# BSU_BQ796XX.net
KiCad netlist of a schematic drawn in Altium Designer
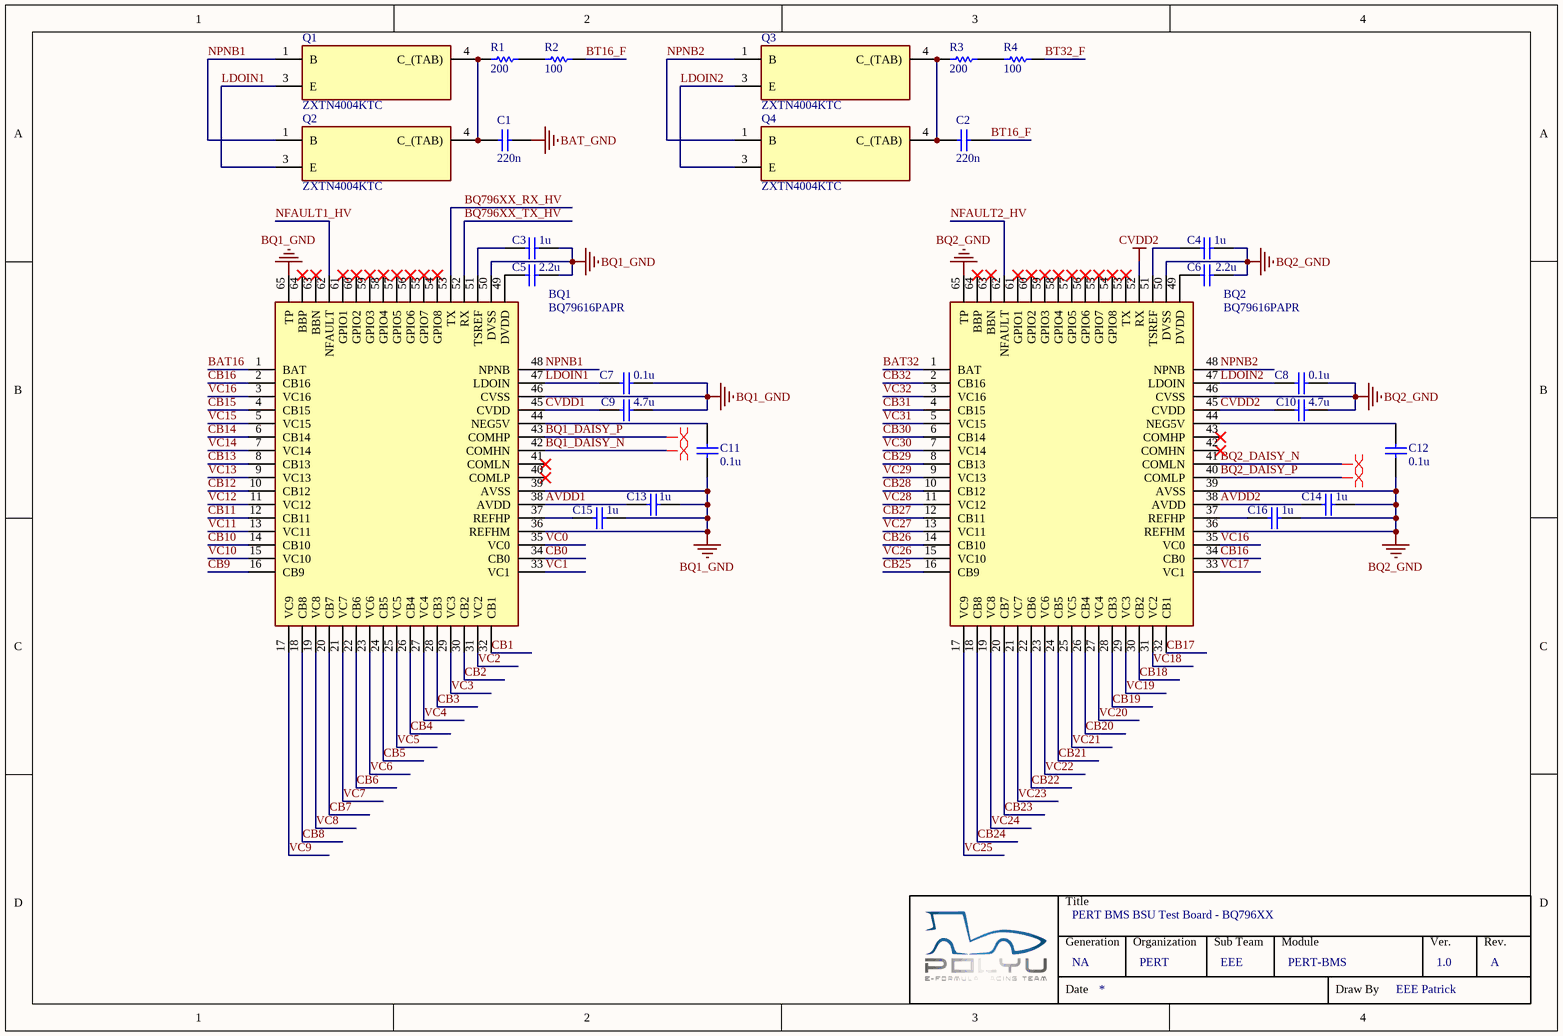
[diagram p0: BSU_BQ796XX.SchDoc]

(export (version "E")
  (design (tool "Eeschema 10.0.6"))
  (components
    (comp (ref "BQ1")
      (value "BQ79616PAPR")
      (footprint "HTQFP65_BQ79616")
      (fields (field (name "MOUSER PART NUMBER") "595-BQ79616PAPR"))
      (libsource (lib "BMS_ShareComponentLibrary") (part "BQ79616PAPR"))
    )
    (comp (ref "BQ2")
      (value "BQ79616PAPR")
      (footprint "HTQFP65_BQ79616")
      (fields (field (name "MOUSER PART NUMBER") "595-BQ79616PAPR"))
      (libsource (lib "BMS_ShareComponentLibrary") (part "BQ79616PAPR"))
    )
    (comp (ref "C1")
      (value "220n")
      (footprint "1210_SMD_C")
      (description "1210 SMD Capacitor")
      (libsource (lib "BMS_ShareComponentLibrary") (part "1210_SMD_Capacitor"))
    )
    (comp (ref "C2")
      (value "220n")
      (footprint "1210_SMD_C")
      (description "1210 SMD Capacitor")
      (libsource (lib "BMS_ShareComponentLibrary") (part "1210_SMD_Capacitor"))
    )
    (comp (ref "C3")
      (value "1u")
      (footprint "0603_SMD_C")
      (description "0603 SMD Capacitor")
      (libsource (lib "BMS_ShareComponentLibrary") (part "0603_SMD_Capacitor"))
    )
    (comp (ref "C4")
      (value "1u")
      (footprint "0603_SMD_C")
      (description "0603 SMD Capacitor")
      (libsource (lib "BMS_ShareComponentLibrary") (part "0603_SMD_Capacitor"))
    )
    (comp (ref "C5")
      (value "2.2u")
      (footprint "0603_SMD_C")
      (description "0603 SMD Capacitor")
      (libsource (lib "BMS_ShareComponentLibrary") (part "0603_SMD_Capacitor"))
    )
    (comp (ref "C6")
      (value "2.2u")
      (footprint "0603_SMD_C")
      (description "0603 SMD Capacitor")
      (libsource (lib "BMS_ShareComponentLibrary") (part "0603_SMD_Capacitor"))
    )
    (comp (ref "C7")
      (value "0.1u")
      (footprint "0603_SMD_C")
      (description "0603 SMD Capacitor")
      (libsource (lib "BMS_ShareComponentLibrary") (part "0603_SMD_Capacitor"))
    )
    (comp (ref "C8")
      (value "0.1u")
      (footprint "0603_SMD_C")
      (description "0603 SMD Capacitor")
      (libsource (lib "BMS_ShareComponentLibrary") (part "0603_SMD_Capacitor"))
    )
    (comp (ref "C9")
      (value "4.7u")
      (footprint "0603_SMD_C")
      (description "0603 SMD Capacitor")
      (libsource (lib "BMS_ShareComponentLibrary") (part "0603_SMD_Capacitor"))
    )
    (comp (ref "C10")
      (value "4.7u")
      (footprint "0603_SMD_C")
      (description "0603 SMD Capacitor")
      (libsource (lib "BMS_ShareComponentLibrary") (part "0603_SMD_Capacitor"))
    )
    (comp (ref "C11")
      (value "0.1u")
      (footprint "0603_SMD_C")
      (description "0603 SMD Capacitor")
      (libsource (lib "BMS_ShareComponentLibrary") (part "0603_SMD_Capacitor"))
    )
    (comp (ref "C12")
      (value "0.1u")
      (footprint "0603_SMD_C")
      (description "0603 SMD Capacitor")
      (libsource (lib "BMS_ShareComponentLibrary") (part "0603_SMD_Capacitor"))
    )
    (comp (ref "C13")
      (value "1u")
      (footprint "0603_SMD_C")
      (description "0603 SMD Capacitor")
      (libsource (lib "BMS_ShareComponentLibrary") (part "0603_SMD_Capacitor"))
    )
    (comp (ref "C14")
      (value "1u")
      (footprint "0603_SMD_C")
      (description "0603 SMD Capacitor")
      (libsource (lib "BMS_ShareComponentLibrary") (part "0603_SMD_Capacitor"))
    )
    (comp (ref "C15")
      (value "1u")
      (footprint "0603_SMD_C")
      (description "0603 SMD Capacitor")
      (libsource (lib "BMS_ShareComponentLibrary") (part "0603_SMD_Capacitor"))
    )
    (comp (ref "C16")
      (value "1u")
      (footprint "0603_SMD_C")
      (description "0603 SMD Capacitor")
      (libsource (lib "BMS_ShareComponentLibrary") (part "0603_SMD_Capacitor"))
    )
    (comp (ref "Q1")
      (value "ZXTN4004KTC")
      (footprint "TO252-3_ZXTN4004K")
      (description "Transistor")
      (fields (field (name "MOUSER PART NUMBER") "621-ZXTN4004KTC"))
      (libsource (lib "BMS_ShareComponentLibrary") (part "ZXTN4004KTC"))
    )
    (comp (ref "Q2")
      (value "ZXTN4004KTC")
      (footprint "TO252-3_ZXTN4004K")
      (description "Transistor")
      (fields (field (name "MOUSER PART NUMBER") "621-ZXTN4004KTC"))
      (libsource (lib "BMS_ShareComponentLibrary") (part "ZXTN4004KTC"))
    )
    (comp (ref "Q3")
      (value "ZXTN4004KTC")
      (footprint "TO252-3_ZXTN4004K")
      (description "Transistor")
      (fields (field (name "MOUSER PART NUMBER") "621-ZXTN4004KTC"))
      (libsource (lib "BMS_ShareComponentLibrary") (part "ZXTN4004KTC"))
    )
    (comp (ref "Q4")
      (value "ZXTN4004KTC")
      (footprint "TO252-3_ZXTN4004K")
      (description "Transistor")
      (fields (field (name "MOUSER PART NUMBER") "621-ZXTN4004KTC"))
      (libsource (lib "BMS_ShareComponentLibrary") (part "ZXTN4004KTC"))
    )
    (comp (ref "R1")
      (value "200")
      (footprint "2010_SMD_R")
      (description "2010 SMD Resistor")
      (libsource (lib "BMS_ShareComponentLibrary") (part "2010_SMD_Resistor"))
    )
    (comp (ref "R2")
      (value "100")
      (footprint "2010_SMD_R")
      (description "2010 SMD Resistor")
      (libsource (lib "BMS_ShareComponentLibrary") (part "2010_SMD_Resistor"))
    )
    (comp (ref "R3")
      (value "200")
      (footprint "2010_SMD_R")
      (description "2010 SMD Resistor")
      (libsource (lib "BMS_ShareComponentLibrary") (part "2010_SMD_Resistor"))
    )
    (comp (ref "R4")
      (value "100")
      (footprint "2010_SMD_R")
      (description "2010 SMD Resistor")
      (libsource (lib "BMS_ShareComponentLibrary") (part "2010_SMD_Resistor"))
    )
  )
  (nets
    (net (code "1") (name "/AVDD1") (class "Default")
      (node (ref "BQ1") (pin "38") (pinfunction "AVDD_38") (pintype "passive"))
      (node (ref "C13") (pin "2") (pinfunction "2_2") (pintype "passive"))
    )
    (net (code "2") (name "/AVDD2") (class "Default")
      (node (ref "BQ2") (pin "38") (pinfunction "AVDD_38") (pintype "passive"))
      (node (ref "C14") (pin "2") (pinfunction "2_2") (pintype "passive"))
    )
    (net (code "3") (name "/BAT16") (class "Default")
      (node (ref "BQ1") (pin "1") (pinfunction "BAT_1") (pintype "passive"))
    )
    (net (code "4") (name "/BAT32") (class "Default")
      (node (ref "BQ2") (pin "1") (pinfunction "BAT_1") (pintype "passive"))
    )
    (net (code "5") (name "/BQ1_DAISY_N") (class "Default")
      (node (ref "BQ1") (pin "42") (pinfunction "COMHN_42") (pintype "passive"))
    )
    (net (code "6") (name "/BQ1_DAISY_P") (class "Default")
      (node (ref "BQ1") (pin "43") (pinfunction "COMHP_43") (pintype "passive"))
    )
    (net (code "7") (name "/BQ2_DAISY_N") (class "Default")
      (node (ref "BQ2") (pin "41") (pinfunction "COMLN_41") (pintype "passive"))
    )
    (net (code "8") (name "/BQ2_DAISY_P") (class "Default")
      (node (ref "BQ2") (pin "40") (pinfunction "COMLP_40") (pintype "passive"))
    )
    (net (code "9") (name "/BQ796XX_RX_HV") (class "Default")
      (node (ref "BQ1") (pin "53") (pinfunction "TX_53") (pintype "passive"))
    )
    (net (code "10") (name "/BQ796XX_TX_HV") (class "Default")
      (node (ref "BQ1") (pin "52") (pinfunction "RX_52") (pintype "passive"))
    )
    (net (code "11") (name "/BT16_F") (class "Default")
      (node (ref "C2") (pin "2") (pinfunction "2_2") (pintype "passive"))
      (node (ref "R2") (pin "2") (pinfunction "2_2") (pintype "passive"))
    )
    (net (code "12") (name "/BT32_F") (class "Default")
      (node (ref "R4") (pin "2") (pinfunction "2_2") (pintype "passive"))
    )
    (net (code "13") (name "/CB0") (class "Default")
      (node (ref "BQ1") (pin "34") (pinfunction "CB0_34") (pintype "passive"))
    )
    (net (code "14") (name "/CB1") (class "Default")
      (node (ref "BQ1") (pin "32") (pinfunction "CB1_32") (pintype "passive"))
    )
    (net (code "15") (name "/CB2") (class "Default")
      (node (ref "BQ1") (pin "30") (pinfunction "CB2_30") (pintype "passive"))
    )
    (net (code "16") (name "/CB3") (class "Default")
      (node (ref "BQ1") (pin "28") (pinfunction "CB3_28") (pintype "passive"))
    )
    (net (code "17") (name "/CB4") (class "Default")
      (node (ref "BQ1") (pin "26") (pinfunction "CB4_26") (pintype "passive"))
    )
    (net (code "18") (name "/CB5") (class "Default")
      (node (ref "BQ1") (pin "24") (pinfunction "CB5_24") (pintype "passive"))
    )
    (net (code "19") (name "/CB6") (class "Default")
      (node (ref "BQ1") (pin "22") (pinfunction "CB6_22") (pintype "passive"))
    )
    (net (code "20") (name "/CB7") (class "Default")
      (node (ref "BQ1") (pin "20") (pinfunction "CB7_20") (pintype "passive"))
    )
    (net (code "21") (name "/CB8") (class "Default")
      (node (ref "BQ1") (pin "18") (pinfunction "CB8_18") (pintype "passive"))
    )
    (net (code "22") (name "/CB9") (class "Default")
      (node (ref "BQ1") (pin "16") (pinfunction "CB9_16") (pintype "passive"))
    )
    (net (code "23") (name "/CB10") (class "Default")
      (node (ref "BQ1") (pin "14") (pinfunction "CB10_14") (pintype "passive"))
    )
    (net (code "24") (name "/CB11") (class "Default")
      (node (ref "BQ1") (pin "12") (pinfunction "CB11_12") (pintype "passive"))
    )
    (net (code "25") (name "/CB12") (class "Default")
      (node (ref "BQ1") (pin "10") (pinfunction "CB12_10") (pintype "passive"))
    )
    (net (code "26") (name "/CB13") (class "Default")
      (node (ref "BQ1") (pin "8") (pinfunction "CB13_8") (pintype "passive"))
    )
    (net (code "27") (name "/CB14") (class "Default")
      (node (ref "BQ1") (pin "6") (pinfunction "CB14_6") (pintype "passive"))
    )
    (net (code "28") (name "/CB15") (class "Default")
      (node (ref "BQ1") (pin "4") (pinfunction "CB15_4") (pintype "passive"))
    )
    (net (code "29") (name "/CB16") (class "Default")
      (node (ref "BQ1") (pin "2") (pinfunction "CB16_2") (pintype "passive"))
      (node (ref "BQ2") (pin "34") (pinfunction "CB0_34") (pintype "passive"))
    )
    (net (code "30") (name "/CB17") (class "Default")
      (node (ref "BQ2") (pin "32") (pinfunction "CB1_32") (pintype "passive"))
    )
    (net (code "31") (name "/CB18") (class "Default")
      (node (ref "BQ2") (pin "30") (pinfunction "CB2_30") (pintype "passive"))
    )
    (net (code "32") (name "/CB19") (class "Default")
      (node (ref "BQ2") (pin "28") (pinfunction "CB3_28") (pintype "passive"))
    )
    (net (code "33") (name "/CB20") (class "Default")
      (node (ref "BQ2") (pin "26") (pinfunction "CB4_26") (pintype "passive"))
    )
    (net (code "34") (name "/CB21") (class "Default")
      (node (ref "BQ2") (pin "24") (pinfunction "CB5_24") (pintype "passive"))
    )
    (net (code "35") (name "/CB22") (class "Default")
      (node (ref "BQ2") (pin "22") (pinfunction "CB6_22") (pintype "passive"))
    )
    (net (code "36") (name "/CB23") (class "Default")
      (node (ref "BQ2") (pin "20") (pinfunction "CB7_20") (pintype "passive"))
    )
    (net (code "37") (name "/CB24") (class "Default")
      (node (ref "BQ2") (pin "18") (pinfunction "CB8_18") (pintype "passive"))
    )
    (net (code "38") (name "/CB25") (class "Default")
      (node (ref "BQ2") (pin "16") (pinfunction "CB9_16") (pintype "passive"))
    )
    (net (code "39") (name "/CB26") (class "Default")
      (node (ref "BQ2") (pin "14") (pinfunction "CB10_14") (pintype "passive"))
    )
    (net (code "40") (name "/CB27") (class "Default")
      (node (ref "BQ2") (pin "12") (pinfunction "CB11_12") (pintype "passive"))
    )
    (net (code "41") (name "/CB28") (class "Default")
      (node (ref "BQ2") (pin "10") (pinfunction "CB12_10") (pintype "passive"))
    )
    (net (code "42") (name "/CB29") (class "Default")
      (node (ref "BQ2") (pin "8") (pinfunction "CB13_8") (pintype "passive"))
    )
    (net (code "43") (name "/CB30") (class "Default")
      (node (ref "BQ2") (pin "6") (pinfunction "CB14_6") (pintype "passive"))
    )
    (net (code "44") (name "/CB31") (class "Default")
      (node (ref "BQ2") (pin "4") (pinfunction "CB15_4") (pintype "passive"))
    )
    (net (code "45") (name "/CB32") (class "Default")
      (node (ref "BQ2") (pin "2") (pinfunction "CB16_2") (pintype "passive"))
    )
    (net (code "46") (name "/CVDD1") (class "Default")
      (node (ref "BQ1") (pin "45") (pinfunction "CVDD_45") (pintype "passive"))
      (node (ref "C9") (pin "1") (pinfunction "1_1") (pintype "passive"))
    )
    (net (code "47") (name "/LDOIN1") (class "Default")
      (node (ref "BQ1") (pin "47") (pinfunction "LDOIN_47") (pintype "passive"))
      (node (ref "C7") (pin "2") (pinfunction "2_2") (pintype "passive"))
      (node (ref "Q1") (pin "3") (pinfunction "E_3") (pintype "passive"))
      (node (ref "Q2") (pin "3") (pinfunction "E_3") (pintype "passive"))
    )
    (net (code "48") (name "/LDOIN2") (class "Default")
      (node (ref "BQ2") (pin "47") (pinfunction "LDOIN_47") (pintype "passive"))
      (node (ref "C8") (pin "2") (pinfunction "2_2") (pintype "passive"))
      (node (ref "Q3") (pin "3") (pinfunction "E_3") (pintype "passive"))
      (node (ref "Q4") (pin "3") (pinfunction "E_3") (pintype "passive"))
    )
    (net (code "49") (name "/NFAULT1_HV") (class "Default")
      (node (ref "BQ1") (pin "62") (pinfunction "NFAULT_62") (pintype "passive"))
    )
    (net (code "50") (name "/NFAULT2_HV") (class "Default")
      (node (ref "BQ2") (pin "62") (pinfunction "NFAULT_62") (pintype "passive"))
    )
    (net (code "51") (name "/NPNB1") (class "Default")
      (node (ref "BQ1") (pin "48") (pinfunction "NPNB_48") (pintype "passive"))
      (node (ref "Q1") (pin "1") (pinfunction "B_1") (pintype "passive"))
      (node (ref "Q2") (pin "1") (pinfunction "B_1") (pintype "passive"))
    )
    (net (code "52") (name "/NPNB2") (class "Default")
      (node (ref "BQ2") (pin "48") (pinfunction "NPNB_48") (pintype "passive"))
      (node (ref "Q3") (pin "1") (pinfunction "B_1") (pintype "passive"))
      (node (ref "Q4") (pin "1") (pinfunction "B_1") (pintype "passive"))
    )
    (net (code "53") (name "/VC0") (class "Default")
      (node (ref "BQ1") (pin "35") (pinfunction "VC0_35") (pintype "passive"))
    )
    (net (code "54") (name "/VC1") (class "Default")
      (node (ref "BQ1") (pin "33") (pinfunction "VC1_33") (pintype "passive"))
    )
    (net (code "55") (name "/VC2") (class "Default")
      (node (ref "BQ1") (pin "31") (pinfunction "VC2_31") (pintype "passive"))
    )
    (net (code "56") (name "/VC3") (class "Default")
      (node (ref "BQ1") (pin "29") (pinfunction "VC3_29") (pintype "passive"))
    )
    (net (code "57") (name "/VC4") (class "Default")
      (node (ref "BQ1") (pin "27") (pinfunction "VC4_27") (pintype "passive"))
    )
    (net (code "58") (name "/VC5") (class "Default")
      (node (ref "BQ1") (pin "25") (pinfunction "VC5_25") (pintype "passive"))
    )
    (net (code "59") (name "/VC6") (class "Default")
      (node (ref "BQ1") (pin "23") (pinfunction "VC6_23") (pintype "passive"))
    )
    (net (code "60") (name "/VC7") (class "Default")
      (node (ref "BQ1") (pin "21") (pinfunction "VC7_21") (pintype "passive"))
    )
    (net (code "61") (name "/VC8") (class "Default")
      (node (ref "BQ1") (pin "19") (pinfunction "VC8_19") (pintype "passive"))
    )
    (net (code "62") (name "/VC9") (class "Default")
      (node (ref "BQ1") (pin "17") (pinfunction "VC9_17") (pintype "passive"))
    )
    (net (code "63") (name "/VC10") (class "Default")
      (node (ref "BQ1") (pin "15") (pinfunction "VC10_15") (pintype "passive"))
    )
    (net (code "64") (name "/VC11") (class "Default")
      (node (ref "BQ1") (pin "13") (pinfunction "VC11_13") (pintype "passive"))
    )
    (net (code "65") (name "/VC12") (class "Default")
      (node (ref "BQ1") (pin "11") (pinfunction "VC12_11") (pintype "passive"))
    )
    (net (code "66") (name "/VC13") (class "Default")
      (node (ref "BQ1") (pin "9") (pinfunction "VC13_9") (pintype "passive"))
    )
    (net (code "67") (name "/VC14") (class "Default")
      (node (ref "BQ1") (pin "7") (pinfunction "VC14_7") (pintype "passive"))
    )
    (net (code "68") (name "/VC15") (class "Default")
      (node (ref "BQ1") (pin "5") (pinfunction "VC15_5") (pintype "passive"))
    )
    (net (code "69") (name "/VC16") (class "Default")
      (node (ref "BQ1") (pin "3") (pinfunction "VC16_3") (pintype "passive"))
      (node (ref "BQ2") (pin "35") (pinfunction "VC0_35") (pintype "passive"))
    )
    (net (code "70") (name "/VC17") (class "Default")
      (node (ref "BQ2") (pin "33") (pinfunction "VC1_33") (pintype "passive"))
    )
    (net (code "71") (name "/VC18") (class "Default")
      (node (ref "BQ2") (pin "31") (pinfunction "VC2_31") (pintype "passive"))
    )
    (net (code "72") (name "/VC19") (class "Default")
      (node (ref "BQ2") (pin "29") (pinfunction "VC3_29") (pintype "passive"))
    )
    (net (code "73") (name "/VC20") (class "Default")
      (node (ref "BQ2") (pin "27") (pinfunction "VC4_27") (pintype "passive"))
    )
    (net (code "74") (name "/VC21") (class "Default")
      (node (ref "BQ2") (pin "25") (pinfunction "VC5_25") (pintype "passive"))
    )
    (net (code "75") (name "/VC22") (class "Default")
      (node (ref "BQ2") (pin "23") (pinfunction "VC6_23") (pintype "passive"))
    )
    (net (code "76") (name "/VC23") (class "Default")
      (node (ref "BQ2") (pin "21") (pinfunction "VC7_21") (pintype "passive"))
    )
    (net (code "77") (name "/VC24") (class "Default")
      (node (ref "BQ2") (pin "19") (pinfunction "VC8_19") (pintype "passive"))
    )
    (net (code "78") (name "/VC25") (class "Default")
      (node (ref "BQ2") (pin "17") (pinfunction "VC9_17") (pintype "passive"))
    )
    (net (code "79") (name "/VC26") (class "Default")
      (node (ref "BQ2") (pin "15") (pinfunction "VC10_15") (pintype "passive"))
    )
    (net (code "80") (name "/VC27") (class "Default")
      (node (ref "BQ2") (pin "13") (pinfunction "VC11_13") (pintype "passive"))
    )
    (net (code "81") (name "/VC28") (class "Default")
      (node (ref "BQ2") (pin "11") (pinfunction "VC12_11") (pintype "passive"))
    )
    (net (code "82") (name "/VC29") (class "Default")
      (node (ref "BQ2") (pin "9") (pinfunction "VC13_9") (pintype "passive"))
    )
    (net (code "83") (name "/VC30") (class "Default")
      (node (ref "BQ2") (pin "7") (pinfunction "VC14_7") (pintype "passive"))
    )
    (net (code "84") (name "/VC31") (class "Default")
      (node (ref "BQ2") (pin "5") (pinfunction "VC15_5") (pintype "passive"))
    )
    (net (code "85") (name "/VC32") (class "Default")
      (node (ref "BQ2") (pin "3") (pinfunction "VC16_3") (pintype "passive"))
    )
    (net (code "86") (name "BAT_GND") (class "Default")
      (node (ref "C1") (pin "2") (pinfunction "2_2") (pintype "passive"))
    )
    (net (code "87") (name "BQ1_GND") (class "Default")
      (node (ref "BQ1") (pin "36") (pinfunction "REFHM_36") (pintype "passive"))
      (node (ref "BQ1") (pin "39") (pinfunction "AVSS_39") (pintype "passive"))
      (node (ref "BQ1") (pin "46") (pinfunction "CVSS_46") (pintype "passive"))
      (node (ref "BQ1") (pin "50") (pinfunction "DVSS_50") (pintype "passive"))
      (node (ref "BQ1") (pin "65") (pinfunction "TP_65") (pintype "passive"))
      (node (ref "C11") (pin "1") (pinfunction "1_1") (pintype "passive"))
      (node (ref "C13") (pin "1") (pinfunction "1_1") (pintype "passive"))
      (node (ref "C15") (pin "1") (pinfunction "1_1") (pintype "passive"))
      (node (ref "C3") (pin "2") (pinfunction "2_2") (pintype "passive"))
      (node (ref "C5") (pin "2") (pinfunction "2_2") (pintype "passive"))
      (node (ref "C7") (pin "1") (pinfunction "1_1") (pintype "passive"))
      (node (ref "C9") (pin "2") (pinfunction "2_2") (pintype "passive"))
    )
    (net (code "88") (name "BQ2_GND") (class "Default")
      (node (ref "BQ2") (pin "36") (pinfunction "REFHM_36") (pintype "passive"))
      (node (ref "BQ2") (pin "39") (pinfunction "AVSS_39") (pintype "passive"))
      (node (ref "BQ2") (pin "46") (pinfunction "CVSS_46") (pintype "passive"))
      (node (ref "BQ2") (pin "50") (pinfunction "DVSS_50") (pintype "passive"))
      (node (ref "BQ2") (pin "65") (pinfunction "TP_65") (pintype "passive"))
      (node (ref "C10") (pin "2") (pinfunction "2_2") (pintype "passive"))
      (node (ref "C12") (pin "1") (pinfunction "1_1") (pintype "passive"))
      (node (ref "C14") (pin "1") (pinfunction "1_1") (pintype "passive"))
      (node (ref "C16") (pin "1") (pinfunction "1_1") (pintype "passive"))
      (node (ref "C4") (pin "2") (pinfunction "2_2") (pintype "passive"))
      (node (ref "C6") (pin "2") (pinfunction "2_2") (pintype "passive"))
      (node (ref "C8") (pin "1") (pinfunction "1_1") (pintype "passive"))
    )
    (net (code "89") (name "CVDD2") (class "Default")
      (node (ref "BQ2") (pin "45") (pinfunction "CVDD_45") (pintype "passive"))
      (node (ref "BQ2") (pin "52") (pinfunction "RX_52") (pintype "passive"))
      (node (ref "C10") (pin "1") (pinfunction "1_1") (pintype "passive"))
    )
    (net (code "90") (name "Net-(BQ1-DVDD)") (class "Default")
      (node (ref "BQ1") (pin "49") (pinfunction "DVDD_49") (pintype "passive"))
      (node (ref "C5") (pin "1") (pinfunction "1_1") (pintype "passive"))
    )
    (net (code "91") (name "Net-(BQ1-NEG5V)") (class "Default")
      (node (ref "BQ1") (pin "44") (pinfunction "NEG5V_44") (pintype "passive"))
      (node (ref "C11") (pin "2") (pinfunction "2_2") (pintype "passive"))
    )
    (net (code "92") (name "Net-(BQ1-REFHP)") (class "Default")
      (node (ref "BQ1") (pin "37") (pinfunction "REFHP_37") (pintype "passive"))
      (node (ref "C15") (pin "2") (pinfunction "2_2") (pintype "passive"))
    )
    (net (code "93") (name "Net-(BQ1-TSREF)") (class "Default")
      (node (ref "BQ1") (pin "51") (pinfunction "TSREF_51") (pintype "passive"))
      (node (ref "C3") (pin "1") (pinfunction "1_1") (pintype "passive"))
    )
    (net (code "94") (name "Net-(BQ2-DVDD)") (class "Default")
      (node (ref "BQ2") (pin "49") (pinfunction "DVDD_49") (pintype "passive"))
      (node (ref "C6") (pin "1") (pinfunction "1_1") (pintype "passive"))
    )
    (net (code "95") (name "Net-(BQ2-NEG5V)") (class "Default")
      (node (ref "BQ2") (pin "44") (pinfunction "NEG5V_44") (pintype "passive"))
      (node (ref "C12") (pin "2") (pinfunction "2_2") (pintype "passive"))
    )
    (net (code "96") (name "Net-(BQ2-REFHP)") (class "Default")
      (node (ref "BQ2") (pin "37") (pinfunction "REFHP_37") (pintype "passive"))
      (node (ref "C16") (pin "2") (pinfunction "2_2") (pintype "passive"))
    )
    (net (code "97") (name "Net-(BQ2-TSREF)") (class "Default")
      (node (ref "BQ2") (pin "51") (pinfunction "TSREF_51") (pintype "passive"))
      (node (ref "C4") (pin "1") (pinfunction "1_1") (pintype "passive"))
    )
    (net (code "98") (name "Net-(Q1-C_(TAB))") (class "Default")
      (node (ref "C1") (pin "1") (pinfunction "1_1") (pintype "passive"))
      (node (ref "Q1") (pin "4") (pinfunction "C_(TAB)_4") (pintype "passive"))
      (node (ref "Q2") (pin "4") (pinfunction "C_(TAB)_4") (pintype "passive"))
      (node (ref "R1") (pin "1") (pinfunction "1_1") (pintype "passive"))
    )
    (net (code "99") (name "Net-(Q3-C_(TAB))") (class "Default")
      (node (ref "C2") (pin "1") (pinfunction "1_1") (pintype "passive"))
      (node (ref "Q3") (pin "4") (pinfunction "C_(TAB)_4") (pintype "passive"))
      (node (ref "Q4") (pin "4") (pinfunction "C_(TAB)_4") (pintype "passive"))
      (node (ref "R3") (pin "1") (pinfunction "1_1") (pintype "passive"))
    )
    (net (code "100") (name "Net-(R1-Pad2)") (class "Default")
      (node (ref "R1") (pin "2") (pinfunction "2_2") (pintype "passive"))
      (node (ref "R2") (pin "1") (pinfunction "1_1") (pintype "passive"))
    )
    (net (code "101") (name "Net-(R3-Pad2)") (class "Default")
      (node (ref "R3") (pin "2") (pinfunction "2_2") (pintype "passive"))
      (node (ref "R4") (pin "1") (pinfunction "1_1") (pintype "passive"))
    )
    (net (code "102") (name "unconnected-(BQ1-BBN-Pad63)") (class "Default")
      (node (ref "BQ1") (pin "63") (pinfunction "BBN_63") (pintype "passive+no_connect"))
    )
    (net (code "103") (name "unconnected-(BQ1-BBP-Pad64)") (class "Default")
      (node (ref "BQ1") (pin "64") (pinfunction "BBP_64") (pintype "passive+no_connect"))
    )
    (net (code "104") (name "unconnected-(BQ1-COMLN-Pad41)") (class "Default")
      (node (ref "BQ1") (pin "41") (pinfunction "COMLN_41") (pintype "passive+no_connect"))
    )
    (net (code "105") (name "unconnected-(BQ1-COMLP-Pad40)") (class "Default")
      (node (ref "BQ1") (pin "40") (pinfunction "COMLP_40") (pintype "passive+no_connect"))
    )
    (net (code "106") (name "unconnected-(BQ1-GPIO1-Pad61)") (class "Default")
      (node (ref "BQ1") (pin "61") (pinfunction "GPIO1_61") (pintype "passive+no_connect"))
    )
    (net (code "107") (name "unconnected-(BQ1-GPIO2-Pad60)") (class "Default")
      (node (ref "BQ1") (pin "60") (pinfunction "GPIO2_60") (pintype "passive+no_connect"))
    )
    (net (code "108") (name "unconnected-(BQ1-GPIO3-Pad59)") (class "Default")
      (node (ref "BQ1") (pin "59") (pinfunction "GPIO3_59") (pintype "passive+no_connect"))
    )
    (net (code "109") (name "unconnected-(BQ1-GPIO4-Pad58)") (class "Default")
      (node (ref "BQ1") (pin "58") (pinfunction "GPIO4_58") (pintype "passive+no_connect"))
    )
    (net (code "110") (name "unconnected-(BQ1-GPIO5-Pad57)") (class "Default")
      (node (ref "BQ1") (pin "57") (pinfunction "GPIO5_57") (pintype "passive+no_connect"))
    )
    (net (code "111") (name "unconnected-(BQ1-GPIO6-Pad56)") (class "Default")
      (node (ref "BQ1") (pin "56") (pinfunction "GPIO6_56") (pintype "passive+no_connect"))
    )
    (net (code "112") (name "unconnected-(BQ1-GPIO7-Pad55)") (class "Default")
      (node (ref "BQ1") (pin "55") (pinfunction "GPIO7_55") (pintype "passive+no_connect"))
    )
    (net (code "113") (name "unconnected-(BQ1-GPIO8-Pad54)") (class "Default")
      (node (ref "BQ1") (pin "54") (pinfunction "GPIO8_54") (pintype "passive+no_connect"))
    )
    (net (code "114") (name "unconnected-(BQ2-BBN-Pad63)") (class "Default")
      (node (ref "BQ2") (pin "63") (pinfunction "BBN_63") (pintype "passive+no_connect"))
    )
    (net (code "115") (name "unconnected-(BQ2-BBP-Pad64)") (class "Default")
      (node (ref "BQ2") (pin "64") (pinfunction "BBP_64") (pintype "passive+no_connect"))
    )
    (net (code "116") (name "unconnected-(BQ2-COMHN-Pad42)") (class "Default")
      (node (ref "BQ2") (pin "42") (pinfunction "COMHN_42") (pintype "passive+no_connect"))
    )
    (net (code "117") (name "unconnected-(BQ2-COMHP-Pad43)") (class "Default")
      (node (ref "BQ2") (pin "43") (pinfunction "COMHP_43") (pintype "passive+no_connect"))
    )
    (net (code "118") (name "unconnected-(BQ2-GPIO1-Pad61)") (class "Default")
      (node (ref "BQ2") (pin "61") (pinfunction "GPIO1_61") (pintype "passive+no_connect"))
    )
    (net (code "119") (name "unconnected-(BQ2-GPIO2-Pad60)") (class "Default")
      (node (ref "BQ2") (pin "60") (pinfunction "GPIO2_60") (pintype "passive+no_connect"))
    )
    (net (code "120") (name "unconnected-(BQ2-GPIO3-Pad59)") (class "Default")
      (node (ref "BQ2") (pin "59") (pinfunction "GPIO3_59") (pintype "passive+no_connect"))
    )
    (net (code "121") (name "unconnected-(BQ2-GPIO4-Pad58)") (class "Default")
      (node (ref "BQ2") (pin "58") (pinfunction "GPIO4_58") (pintype "passive+no_connect"))
    )
    (net (code "122") (name "unconnected-(BQ2-GPIO5-Pad57)") (class "Default")
      (node (ref "BQ2") (pin "57") (pinfunction "GPIO5_57") (pintype "passive+no_connect"))
    )
    (net (code "123") (name "unconnected-(BQ2-GPIO6-Pad56)") (class "Default")
      (node (ref "BQ2") (pin "56") (pinfunction "GPIO6_56") (pintype "passive+no_connect"))
    )
    (net (code "124") (name "unconnected-(BQ2-GPIO7-Pad55)") (class "Default")
      (node (ref "BQ2") (pin "55") (pinfunction "GPIO7_55") (pintype "passive+no_connect"))
    )
    (net (code "125") (name "unconnected-(BQ2-GPIO8-Pad54)") (class "Default")
      (node (ref "BQ2") (pin "54") (pinfunction "GPIO8_54") (pintype "passive+no_connect"))
    )
    (net (code "126") (name "unconnected-(BQ2-TX-Pad53)") (class "Default")
      (node (ref "BQ2") (pin "53") (pinfunction "TX_53") (pintype "passive+no_connect"))
    )
  )
)
